# Power.net
KiCad netlist of a schematic drawn in Altium Designer
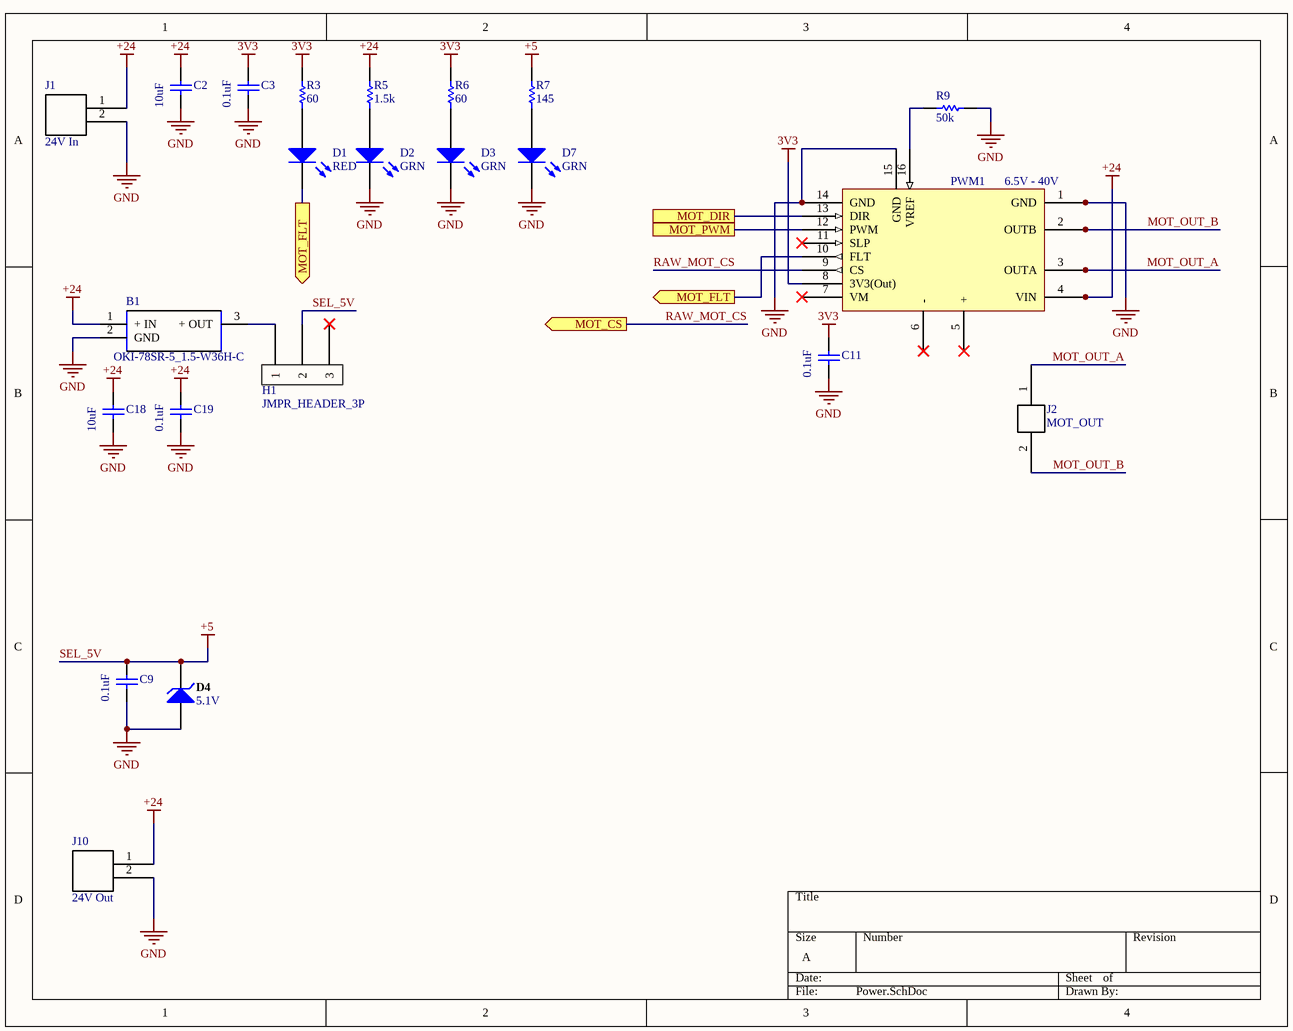
[diagram p0: Power.SchDoc]

(export (version "E")
  (design (tool "Eeschema 10.0.6"))
  (components
    (comp (ref "B1")
      (value "OKI-78SR-5_1.5-W36H-C")
      (footprint "OKI-78SR-HORIZONTAL")
      (description "Switching Regulator 7-36Vin 5Vo 1.5A Non-Isolated DC-DC Converter, 5V dc Output, 1.5A")
      (fields
        (field (name "MOUSER PART NUMBER") "580-OKI78SR51.5W36HC")
        (field (name "MANUFACTURER_PART_NUMBER") "OKI-78SR-5/1.5-W36H-C")
      )
      (libsource (lib "OKI-78SR-5_1.5-W36H-C") (part "OKI-78SR-5_1.5-W36H-C"))
    )
    (comp (ref "C2")
      (value "10uF")
      (footprint "RESC2013X60X35LL10T20")
      (description "Capacitor (Semiconductor SIM Model)")
      (fields (field (name "Comment") "Cap Semi") (field (name "PUBLISHER") "Altium Limited"))
      (libsource (lib "Miscellaneous Devices") (part "Cap Semi"))
    )
    (comp (ref "C3")
      (value "0.1uF")
      (footprint "RESC2013X60X35LL10T20")
      (description "Capacitor (Semiconductor SIM Model)")
      (fields (field (name "Comment") "Cap Semi") (field (name "PUBLISHER") "Altium Limited"))
      (libsource (lib "Miscellaneous Devices") (part "Cap Semi"))
    )
    (comp (ref "C9")
      (value "0.1uF")
      (footprint "RESC2013X60X35LL10T20")
      (description "Capacitor (Semiconductor SIM Model)")
      (fields (field (name "Comment") "Cap Semi") (field (name "PUBLISHER") "Altium Limited"))
      (libsource (lib "Miscellaneous Devices") (part "Cap Semi"))
    )
    (comp (ref "C11")
      (value "0.1uF")
      (footprint "RESC2013X60X35LL10T20")
      (description "Capacitor (Semiconductor SIM Model)")
      (fields (field (name "Comment") "Cap Semi") (field (name "PUBLISHER") "Altium Limited"))
      (libsource (lib "Miscellaneous Devices") (part "Cap Semi"))
    )
    (comp (ref "C18")
      (value "10uF")
      (footprint "RESC2013X60X35LL10T20")
      (description "Capacitor (Semiconductor SIM Model)")
      (fields (field (name "Comment") "Cap Semi") (field (name "PUBLISHER") "Altium Limited"))
      (libsource (lib "Miscellaneous Devices") (part "Cap Semi"))
    )
    (comp (ref "C19")
      (value "0.1uF")
      (footprint "RESC2013X60X35LL10T20")
      (description "Capacitor (Semiconductor SIM Model)")
      (fields (field (name "Comment") "Cap Semi") (field (name "PUBLISHER") "Altium Limited"))
      (libsource (lib "Miscellaneous Devices") (part "Cap Semi"))
    )
    (comp (ref "D1")
      (value "RED")
      (footprint "LED")
      (description "Typical INFRARED GaAs LED")
      (fields (field (name "PUBLISHER") "Altium Limited"))
      (libsource (lib "Miscellaneous Devices") (part "LED0"))
    )
    (comp (ref "D2")
      (value "GRN")
      (footprint "LED")
      (description "Typical INFRARED GaAs LED")
      (fields (field (name "PUBLISHER") "Altium Limited"))
      (libsource (lib "Miscellaneous Devices") (part "LED0"))
    )
    (comp (ref "D3")
      (value "GRN")
      (footprint "LED")
      (description "Typical INFRARED GaAs LED")
      (fields (field (name "PUBLISHER") "Altium Limited"))
      (libsource (lib "Miscellaneous Devices") (part "LED0"))
    )
    (comp (ref "D4")
      (value "5.1V")
      (footprint "VISH-SOD-123-2_V")
      (fields
        (field (name "TOLERANCE") "+/- 5%")
        (field (name "MANUFACTURER") "Vishay Semiconductor")
        (field (name "PARTNUMBER") "MMSZ5232B-E3-08")
      )
      (libsource (lib "Altium Content Vault") (part "VISH-DZEN_A1K2-2"))
    )
    (comp (ref "D7")
      (value "GRN")
      (footprint "LED")
      (description "Typical INFRARED GaAs LED")
      (fields (field (name "PUBLISHER") "Altium Limited"))
      (libsource (lib "Miscellaneous Devices") (part "LED0"))
    )
    (comp (ref "H1")
      (value "JMPR_HEADER_3P")
      (footprint "STD3P")
      (libsource (lib "Jaden") (part "JMPR_HEADER_3P"))
    )
    (comp (ref "J1")
      (value "24V In")
      (footprint "1510482204")
      (description "Molex 6.5MM 2 pin connector, used for power connections. P/N 1510482204 and similar models.")
      (libsource (lib "Molex 6.5MM  power connectors, 1510482204 etc.") (part "Molex 6.5MM 2 pin connector"))
    )
    (comp (ref "J2")
      (value "MOT_OUT")
      (footprint "0430450227")
      (description "Molex micro-fit 3.0. Molex P/N 0430450227")
      (libsource (lib "Molex Micro-Fit 3.0") (part "Molex micro-fit 2-pin"))
    )
    (comp (ref "J10")
      (value "24V Out")
      (footprint "1510482204")
      (description "Molex 6.5MM 2 pin connector, used for power connections. P/N 1510482204 and similar models.")
      (libsource (lib "Molex 6.5MM  power connectors, 1510482204 etc.") (part "Molex 6.5MM 2 pin connector"))
    )
    (comp (ref "PWM1")
      (value "6.5V - 40V")
      (footprint "Pololu_G2_Driver_24v21")
      (libsource (lib "Pololu G2 High-Power Motor Driver 24v21") (part "Pololu G2 High-Power Motor Driver 24v21"))
    )
    (comp (ref "R3")
      (value "60")
      (footprint "RESC2013X60X35LL10T20")
      (libsource (lib "Jaden") (part "RES-2"))
    )
    (comp (ref "R5")
      (value "1.5k")
      (footprint "RESC2013X60X35LL10T20")
      (libsource (lib "Jaden") (part "RES-2"))
    )
    (comp (ref "R6")
      (value "60")
      (footprint "0805:RESC2013X60X35LL10T20")
      (libsource (lib "Jaden") (part "RES-2"))
    )
    (comp (ref "R7")
      (value "145")
      (footprint "0805:RESC2013X60X35LL10T20")
      (libsource (lib "Jaden") (part "RES-2"))
    )
    (comp (ref "R9")
      (value "50k")
      (footprint "0805:RESC2013X60X35LL10T20")
      (libsource (lib "Jaden") (part "RES-2"))
    )
  )
  (nets
    (net (code "1") (name "+5") (class "Default")
      (node (ref "C9") (pin "2") (pinfunction "2_2") (pintype "passive"))
      (node (ref "D4") (pin "2") (pinfunction "K_2") (pintype "passive"))
      (node (ref "H1") (pin "2") (pinfunction "2_2") (pintype "passive"))
      (node (ref "R7") (pin "2") (pinfunction "2_2") (pintype "passive"))
    )
    (net (code "2") (name "+24") (class "Default")
      (node (ref "B1") (pin "1") (pinfunction "+_IN_1") (pintype "passive"))
      (node (ref "C18") (pin "2") (pinfunction "2_2") (pintype "passive"))
      (node (ref "C19") (pin "2") (pinfunction "2_2") (pintype "passive"))
      (node (ref "C2") (pin "2") (pinfunction "2_2") (pintype "passive"))
      (node (ref "J1") (pin "1") (pintype "passive"))
      (node (ref "J10") (pin "1") (pintype "passive"))
      (node (ref "PWM1") (pin "4") (pinfunction "VIN_4") (pintype "power_in"))
      (node (ref "PWM1") (pin "4a") (pinfunction "VIN_4a") (pintype "passive"))
      (node (ref "PWM1") (pin "4b") (pinfunction "VIN_4b") (pintype "passive"))
      (node (ref "R5") (pin "2") (pinfunction "2_2") (pintype "passive"))
    )
    (net (code "4") (name "/MOT_DIR") (class "Default")
      (node (ref "PWM1") (pin "13") (pinfunction "DIR_13") (pintype "input"))
    )
    (net (code "5") (name "/MOT_FLT") (class "Default")
      (node (ref "D1") (pin "2") (pinfunction "K_2") (pintype "passive"))
      (node (ref "PWM1") (pin "10") (pinfunction "FLT_10") (pintype "output"))
    )
    (net (code "6") (name "/MOT_OUT_A") (class "Default")
      (node (ref "J2") (pin "1") (pintype "passive"))
      (node (ref "PWM1") (pin "3") (pinfunction "OUTA_3") (pintype "passive"))
      (node (ref "PWM1") (pin "3a") (pinfunction "OUTA_3a") (pintype "passive"))
      (node (ref "PWM1") (pin "3b") (pinfunction "OUTA_3b") (pintype "power_in"))
    )
    (net (code "7") (name "/MOT_OUT_B") (class "Default")
      (node (ref "J2") (pin "2") (pintype "passive"))
      (node (ref "PWM1") (pin "2") (pinfunction "OUTB_2") (pintype "power_in"))
      (node (ref "PWM1") (pin "2a") (pinfunction "OUTB_2a") (pintype "passive"))
      (node (ref "PWM1") (pin "2b") (pinfunction "OUTB_2b") (pintype "passive"))
    )
    (net (code "8") (name "/MOT_PWM") (class "Default")
      (node (ref "PWM1") (pin "12") (pinfunction "PWM_12") (pintype "input"))
    )
    (net (code "9") (name "/RAW_MOT_CS") (class "Default")
      (node (ref "PWM1") (pin "9") (pinfunction "CS_9") (pintype "output"))
    )
    (net (code "10") (name "3V3") (class "Default")
      (node (ref "C11") (pin "2") (pinfunction "2_2") (pintype "passive"))
      (node (ref "C3") (pin "2") (pinfunction "2_2") (pintype "passive"))
      (node (ref "PWM1") (pin "8") (pinfunction "3V3(Out)_8") (pintype "power_in"))
      (node (ref "R3") (pin "2") (pinfunction "2_2") (pintype "passive"))
      (node (ref "R6") (pin "2") (pinfunction "2_2") (pintype "passive"))
    )
    (net (code "11") (name "GND") (class "Default")
      (node (ref "B1") (pin "2") (pinfunction "GND_2") (pintype "passive"))
      (node (ref "C11") (pin "1") (pinfunction "1_1") (pintype "passive"))
      (node (ref "C18") (pin "1") (pinfunction "1_1") (pintype "passive"))
      (node (ref "C19") (pin "1") (pinfunction "1_1") (pintype "passive"))
      (node (ref "C2") (pin "1") (pinfunction "1_1") (pintype "passive"))
      (node (ref "C3") (pin "1") (pinfunction "1_1") (pintype "passive"))
      (node (ref "C9") (pin "1") (pinfunction "1_1") (pintype "passive"))
      (node (ref "D2") (pin "2") (pinfunction "K_2") (pintype "passive"))
      (node (ref "D3") (pin "2") (pinfunction "K_2") (pintype "passive"))
      (node (ref "D4") (pin "1") (pinfunction "A_1") (pintype "passive"))
      (node (ref "D7") (pin "2") (pinfunction "K_2") (pintype "passive"))
      (node (ref "J1") (pin "2") (pintype "passive"))
      (node (ref "J10") (pin "2") (pintype "passive"))
      (node (ref "PWM1") (pin "1") (pinfunction "GND_1") (pintype "power_in"))
      (node (ref "PWM1") (pin "14") (pinfunction "GND_14") (pintype "power_in"))
      (node (ref "PWM1") (pin "15") (pinfunction "GND_15") (pintype "power_in"))
      (node (ref "PWM1") (pin "1a") (pinfunction "GND_1a") (pintype "passive"))
      (node (ref "PWM1") (pin "1b") (pinfunction "GND_1b") (pintype "passive"))
      (node (ref "R9") (pin "1") (pinfunction "1_1") (pintype "passive"))
    )
    (net (code "12") (name "Net-(B1-+_OUT)") (class "Default")
      (node (ref "B1") (pin "3") (pinfunction "+_OUT_3") (pintype "passive"))
      (node (ref "H1") (pin "1") (pinfunction "1_1") (pintype "passive"))
    )
    (net (code "13") (name "Net-(D1-A)") (class "Default")
      (node (ref "D1") (pin "1") (pinfunction "A_1") (pintype "passive"))
      (node (ref "R3") (pin "1") (pinfunction "1_1") (pintype "passive"))
    )
    (net (code "14") (name "Net-(D2-A)") (class "Default")
      (node (ref "D2") (pin "1") (pinfunction "A_1") (pintype "passive"))
      (node (ref "R5") (pin "1") (pinfunction "1_1") (pintype "passive"))
    )
    (net (code "15") (name "Net-(D3-A)") (class "Default")
      (node (ref "D3") (pin "1") (pinfunction "A_1") (pintype "passive"))
      (node (ref "R6") (pin "1") (pinfunction "1_1") (pintype "passive"))
    )
    (net (code "16") (name "Net-(D7-A)") (class "Default")
      (node (ref "D7") (pin "1") (pinfunction "A_1") (pintype "passive"))
      (node (ref "R7") (pin "1") (pinfunction "1_1") (pintype "passive"))
    )
    (net (code "17") (name "Net-(PWM1-VREF)") (class "Default")
      (node (ref "PWM1") (pin "16") (pinfunction "VREF_16") (pintype "input"))
      (node (ref "R9") (pin "2") (pinfunction "2_2") (pintype "passive"))
    )
    (net (code "18") (name "unconnected-(H1-Pad3)") (class "Default")
      (node (ref "H1") (pin "3") (pinfunction "3_3") (pintype "passive+no_connect"))
    )
    (net (code "19") (name "unconnected-(PWM1-+-Pad5)") (class "Default")
      (node (ref "PWM1") (pin "5") (pinfunction "+_5") (pintype "power_in+no_connect"))
    )
    (net (code "20") (name "unconnected-(PWM1---Pad6)") (class "Default")
      (node (ref "PWM1") (pin "6") (pinfunction "-_6") (pintype "power_in+no_connect"))
    )
    (net (code "21") (name "unconnected-(PWM1-SLP-Pad11)") (class "Default")
      (node (ref "PWM1") (pin "11") (pinfunction "SLP_11") (pintype "input+no_connect"))
    )
    (net (code "22") (name "unconnected-(PWM1-VM-Pad7)") (class "Default")
      (node (ref "PWM1") (pin "7") (pinfunction "VM_7") (pintype "power_in+no_connect"))
    )
  )
)
